# S7CAS-PLEIADES-CARTE-MERE_P20_Flash-Sens.net
KiCad netlist of a schematic drawn in Altium Designer
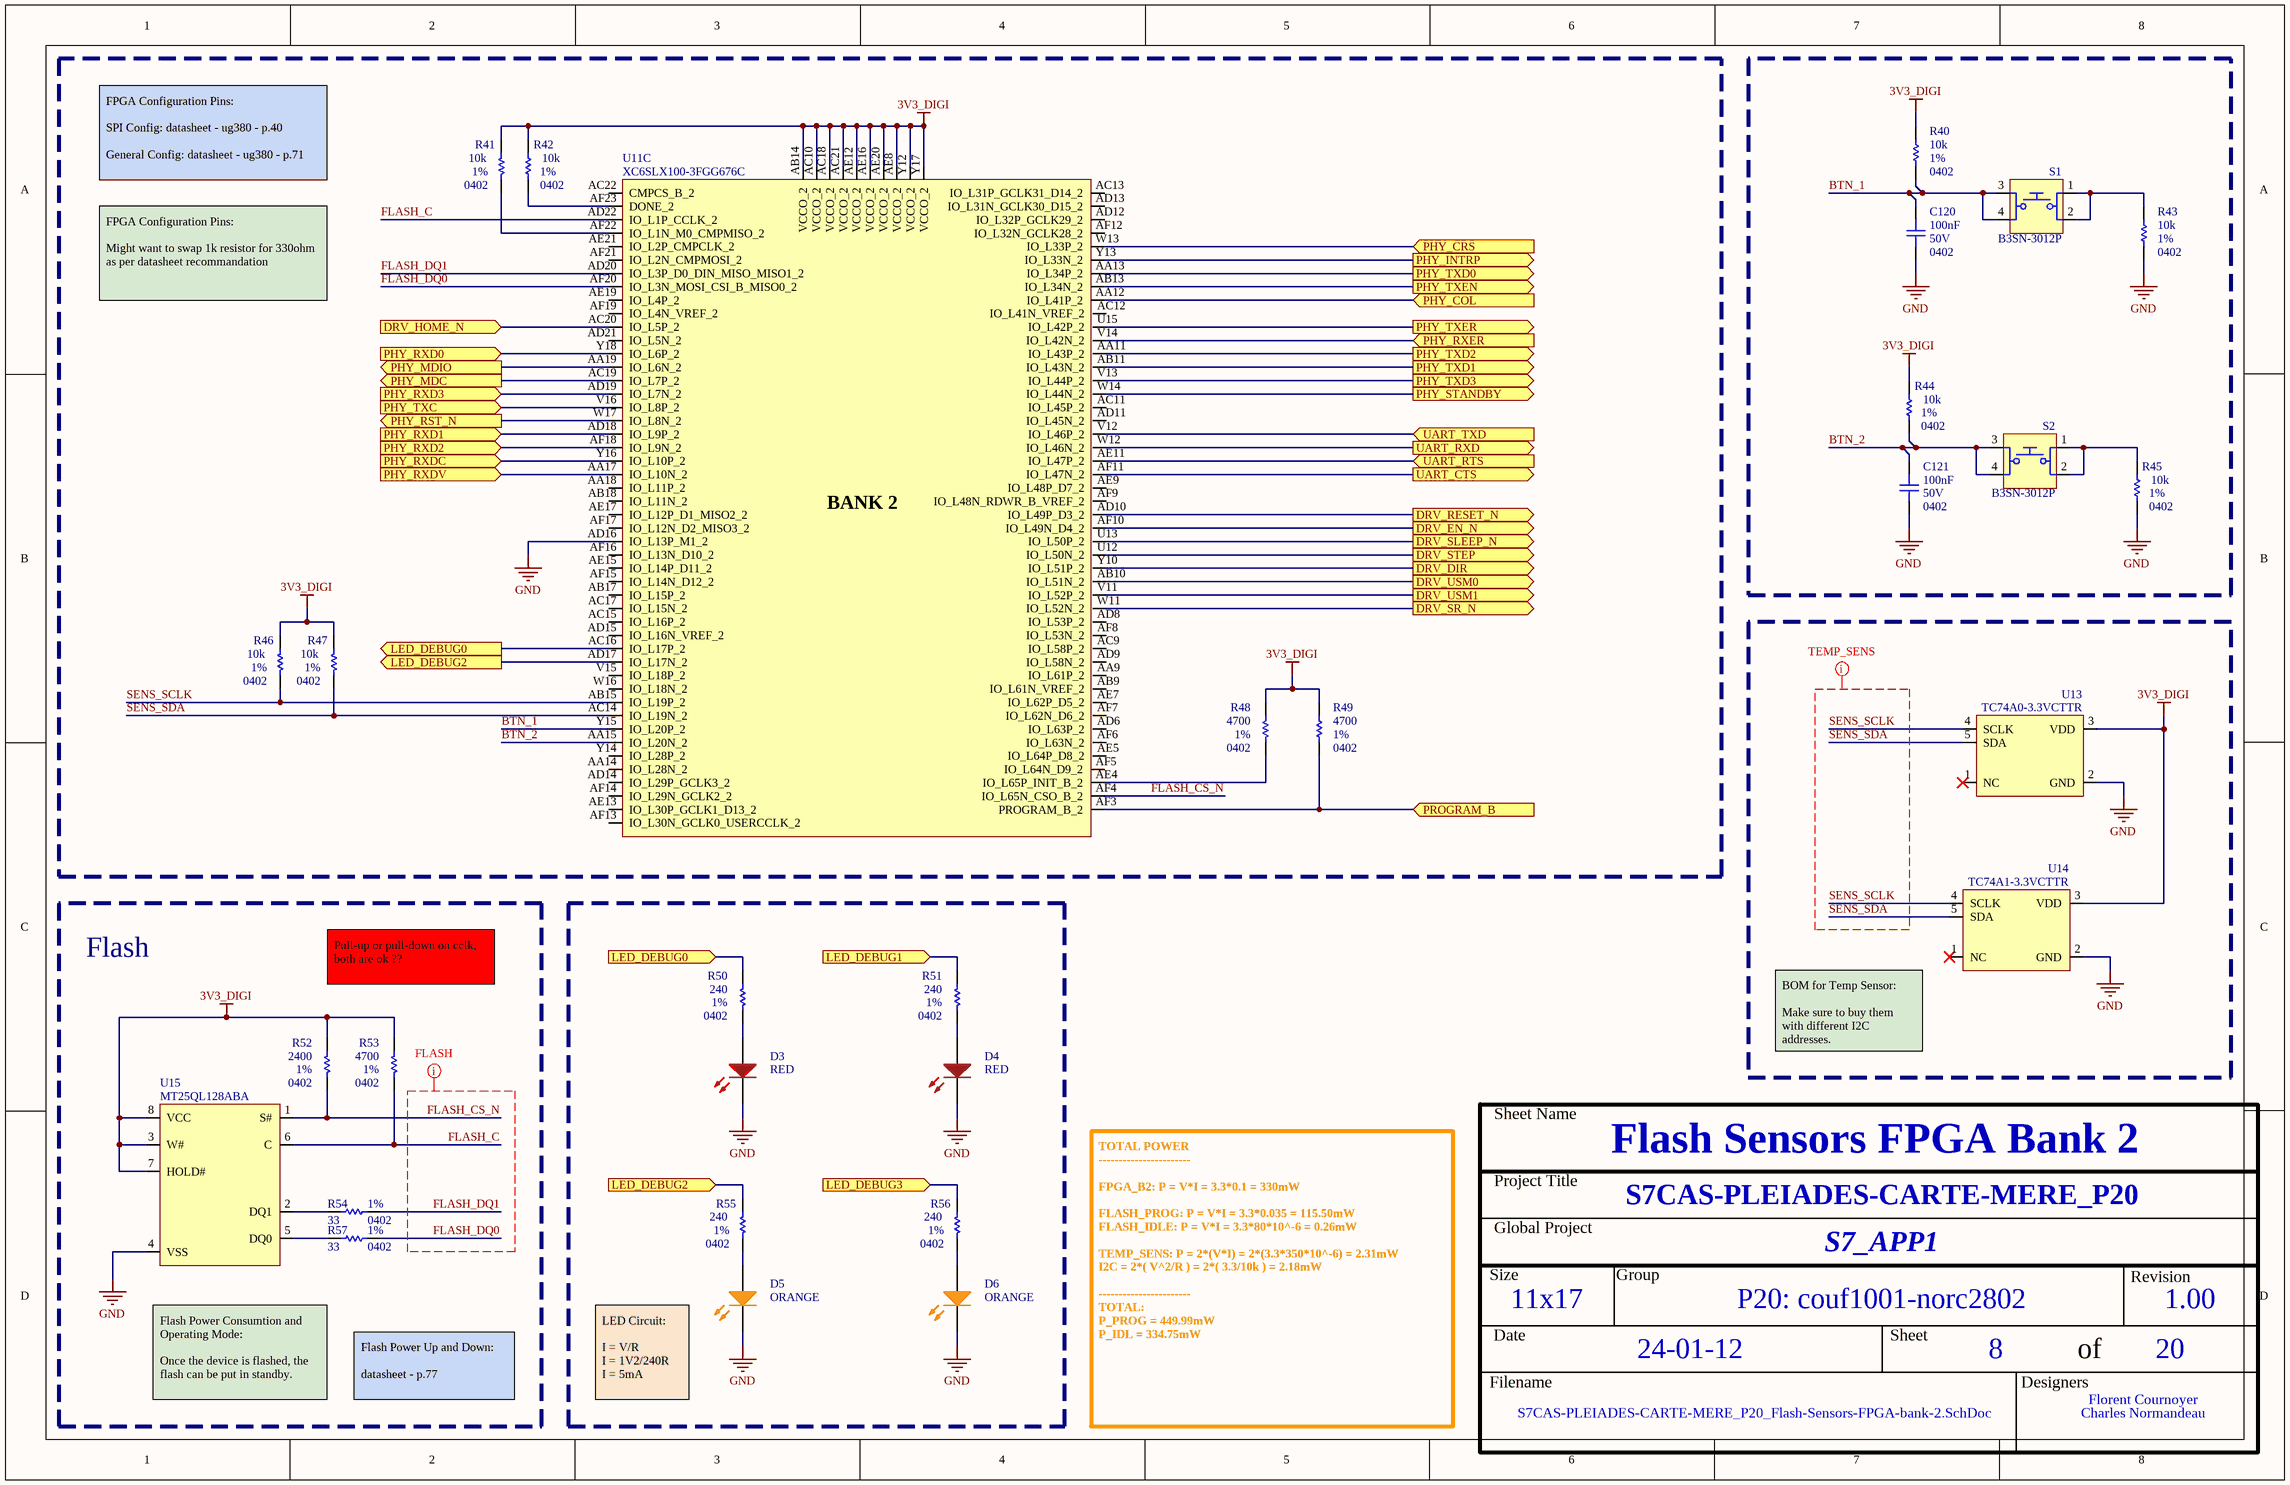
[diagram p0: S7CAS-PLEIADES-CARTE-MERE_P20_Flash-Sensors-FPGA-bank-2.SchDoc]

(export (version "E")
  (design (tool "Eeschema 10.0.6"))
  (components
    (comp (ref "C120")
      (value "100nF")
      (footprint "CAP_0402")
      (description "CAP - 0402")
      (fields
        (field (name "MFG PART NUMBER") "GRM155R61H104KE14")
        (field (name "VOLTAGE") "50V")
        (field (name "PACKAGE") "0402")
        (field (name "CREATEDBY") "Jonathan Bouchard")
      )
      (libsource (lib "S7CAS_LIB2023") (part "CAP - 0402"))
    )
    (comp (ref "C121")
      (value "100nF")
      (footprint "CAP_0402")
      (description "CAP - 0402")
      (fields
        (field (name "MFG PART NUMBER") "GRM155R61H104KE14")
        (field (name "VOLTAGE") "50V")
        (field (name "PACKAGE") "0402")
        (field (name "CREATEDBY") "Jonathan Bouchard")
      )
      (libsource (lib "S7CAS_LIB2023") (part "CAP - 0402"))
    )
    (comp (ref "D3")
      (value "RED")
      (footprint "LED_0603")
      (description "LED - 620nM RED 2mA - 0603")
      (fields
        (field (name "VOLTAGE") "1.8V")
        (field (name "MFG") "ROHM Semiconductor")
        (field (name "CREATEDBY") "Jonathan Bouchard")
      )
      (libsource (lib "S7CAS_LIB2023") (part "LED_SML-311UTT86"))
    )
    (comp (ref "D4")
      (value "RED")
      (footprint "LED_0603")
      (description "LED - 620nM RED 2mA - 0603")
      (fields
        (field (name "VOLTAGE") "1.8V")
        (field (name "MFG") "ROHM Semiconductor")
        (field (name "CREATEDBY") "Jonathan Bouchard")
      )
      (libsource (lib "S7CAS_LIB2023") (part "LED_SML-311UTT86"))
    )
    (comp (ref "D5")
      (value "ORANGE")
      (footprint "LED_0603")
      (description "LED - 611nM ORANGE 2mA - 0603")
      (fields
        (field (name "VOLTAGE") "1.8V")
        (field (name "MFG") "ROHM Semiconductor")
        (field (name "CREATEDBY") "Jonathan Bouchard")
      )
      (libsource (lib "S7CAS_LIB2023") (part "LED_SML-311DTT86"))
    )
    (comp (ref "D6")
      (value "ORANGE")
      (footprint "LED_0603")
      (description "LED - 611nM ORANGE 2mA - 0603")
      (fields
        (field (name "VOLTAGE") "1.8V")
        (field (name "MFG") "ROHM Semiconductor")
        (field (name "CREATEDBY") "Jonathan Bouchard")
      )
      (libsource (lib "S7CAS_LIB2023") (part "LED_SML-311DTT86"))
    )
    (comp (ref "R40")
      (value "10k")
      (footprint "RES_0402")
      (description "RES - 0402")
      (fields
        (field (name "VOLTAGE") "50V")
        (field (name "MFG PART NUMBER") "MCS04020C1002FE000")
        (field (name "PACKAGE") "0402")
        (field (name "PRECISION") "1%")
        (field (name "CREATEDBY") "Jonathan Bouchard")
      )
      (libsource (lib "S7CAS_LIB2023") (part "RES - 0402"))
    )
    (comp (ref "R41")
      (value "10k")
      (footprint "RES_0402")
      (description "RES - 0402")
      (fields
        (field (name "VOLTAGE") "50V")
        (field (name "MFG PART NUMBER") "MCS04020C1002FE000")
        (field (name "PACKAGE") "0402")
        (field (name "PRECISION") "1%")
        (field (name "CREATEDBY") "Jonathan Bouchard")
      )
      (libsource (lib "S7CAS_LIB2023") (part "RES - 0402"))
    )
    (comp (ref "R42")
      (value "10k")
      (footprint "RES_0402")
      (description "RES - 0402")
      (fields
        (field (name "VOLTAGE") "50V")
        (field (name "MFG PART NUMBER") "MCS04020C1002FE000")
        (field (name "PACKAGE") "0402")
        (field (name "PRECISION") "1%")
        (field (name "CREATEDBY") "Jonathan Bouchard")
      )
      (libsource (lib "S7CAS_LIB2023") (part "RES - 0402"))
    )
    (comp (ref "R43")
      (value "10k")
      (footprint "RES_0402")
      (description "RES - 0402")
      (fields
        (field (name "VOLTAGE") "50V")
        (field (name "MFG PART NUMBER") "MCS04020C1002FE000")
        (field (name "PACKAGE") "0402")
        (field (name "PRECISION") "1%")
        (field (name "CREATEDBY") "Jonathan Bouchard")
      )
      (libsource (lib "S7CAS_LIB2023") (part "RES - 0402"))
    )
    (comp (ref "R44")
      (value "10k")
      (footprint "RES_0402")
      (description "RES - 0402")
      (fields
        (field (name "VOLTAGE") "50V")
        (field (name "MFG PART NUMBER") "MCS04020C1002FE000")
        (field (name "PACKAGE") "0402")
        (field (name "PRECISION") "1%")
        (field (name "CREATEDBY") "Jonathan Bouchard")
      )
      (libsource (lib "S7CAS_LIB2023") (part "RES - 0402"))
    )
    (comp (ref "R45")
      (value "10k")
      (footprint "RES_0402")
      (description "RES - 0402")
      (fields
        (field (name "VOLTAGE") "50V")
        (field (name "MFG PART NUMBER") "MCS04020C1002FE000")
        (field (name "PACKAGE") "0402")
        (field (name "PRECISION") "1%")
        (field (name "CREATEDBY") "Jonathan Bouchard")
      )
      (libsource (lib "S7CAS_LIB2023") (part "RES - 0402"))
    )
    (comp (ref "R46")
      (value "10k")
      (footprint "RES_0402")
      (description "RES - 0402")
      (fields
        (field (name "VOLTAGE") "50V")
        (field (name "MFG PART NUMBER") "MCS04020C1002FE000")
        (field (name "PACKAGE") "0402")
        (field (name "PRECISION") "1%")
        (field (name "CREATEDBY") "Jonathan Bouchard")
      )
      (libsource (lib "S7CAS_LIB2023") (part "RES - 0402"))
    )
    (comp (ref "R47")
      (value "10k")
      (footprint "RES_0402")
      (description "RES - 0402")
      (fields
        (field (name "VOLTAGE") "50V")
        (field (name "MFG PART NUMBER") "MCS04020C1002FE000")
        (field (name "PACKAGE") "0402")
        (field (name "PRECISION") "1%")
        (field (name "CREATEDBY") "Jonathan Bouchard")
      )
      (libsource (lib "S7CAS_LIB2023") (part "RES - 0402"))
    )
    (comp (ref "R48")
      (value "4700")
      (footprint "RES_0402")
      (description "RES - 0402")
      (fields
        (field (name "VOLTAGE") "50V")
        (field (name "MFG PART NUMBER") "TBD")
        (field (name "PACKAGE") "0402")
        (field (name "PRECISION") "1%")
        (field (name "CREATEDBY") "Jonathan Bouchard")
      )
      (libsource (lib "S7CAS_LIB2023") (part "RES - 0402"))
    )
    (comp (ref "R49")
      (value "4700")
      (footprint "RES_0402")
      (description "RES - 0402")
      (fields
        (field (name "VOLTAGE") "50V")
        (field (name "MFG PART NUMBER") "TBD")
        (field (name "PACKAGE") "0402")
        (field (name "PRECISION") "1%")
        (field (name "CREATEDBY") "Jonathan Bouchard")
      )
      (libsource (lib "S7CAS_LIB2023") (part "RES - 0402"))
    )
    (comp (ref "R50")
      (value "240")
      (footprint "RES_0402")
      (description "RES - 0402")
      (fields
        (field (name "VOLTAGE") "50V")
        (field (name "MFG PART NUMBER") "ERA-2AEB241X")
        (field (name "PACKAGE") "0402")
        (field (name "PRECISION") "1%")
        (field (name "CREATEDBY") "Jonathan Bouchard")
      )
      (libsource (lib "S7CAS_LIB2023") (part "RES - 0402"))
    )
    (comp (ref "R51")
      (value "240")
      (footprint "RES_0402")
      (description "RES - 0402")
      (fields
        (field (name "VOLTAGE") "50V")
        (field (name "MFG PART NUMBER") "ERA-2AEB241X")
        (field (name "PACKAGE") "0402")
        (field (name "PRECISION") "1%")
        (field (name "CREATEDBY") "Jonathan Bouchard")
      )
      (libsource (lib "S7CAS_LIB2023") (part "RES - 0402"))
    )
    (comp (ref "R52")
      (value "2400")
      (footprint "RES_0402")
      (description "RES - 0402")
      (fields
        (field (name "VOLTAGE") "50V")
        (field (name "POWER") "1/16W")
        (field (name "PACKAGE") "0402")
        (field (name "PRECISION") "1%")
        (field (name "CREATEDBY") "Jonathan Bouchard")
      )
      (libsource (lib "S7CAS_LIB2023") (part "RES - 0402"))
    )
    (comp (ref "R53")
      (value "4700")
      (footprint "RES_0402")
      (description "RES - 0402")
      (fields
        (field (name "VOLTAGE") "50V")
        (field (name "MFG PART NUMBER") "TBD")
        (field (name "PACKAGE") "0402")
        (field (name "PRECISION") "1%")
        (field (name "CREATEDBY") "Jonathan Bouchard")
      )
      (libsource (lib "S7CAS_LIB2023") (part "RES - 0402"))
    )
    (comp (ref "R54")
      (value "33")
      (footprint "RES_0402")
      (description "RES - 0402")
      (fields
        (field (name "VOLTAGE") "50V")
        (field (name "MFG PART NUMBER") "CRCW040233R0FKEDC")
        (field (name "PACKAGE") "0402")
        (field (name "PRECISION") "1%")
        (field (name "CREATEDBY") "Jonathan Bouchard")
      )
      (libsource (lib "S7CAS_LIB2023") (part "RES - 0402"))
    )
    (comp (ref "R55")
      (value "240")
      (footprint "RES_0402")
      (description "RES - 0402")
      (fields
        (field (name "VOLTAGE") "50V")
        (field (name "MFG PART NUMBER") "ERA-2AEB241X")
        (field (name "PACKAGE") "0402")
        (field (name "PRECISION") "1%")
        (field (name "CREATEDBY") "Jonathan Bouchard")
      )
      (libsource (lib "S7CAS_LIB2023") (part "RES - 0402"))
    )
    (comp (ref "R56")
      (value "240")
      (footprint "RES_0402")
      (description "RES - 0402")
      (fields
        (field (name "VOLTAGE") "50V")
        (field (name "MFG PART NUMBER") "ERA-2AEB241X")
        (field (name "PACKAGE") "0402")
        (field (name "PRECISION") "1%")
        (field (name "CREATEDBY") "Jonathan Bouchard")
      )
      (libsource (lib "S7CAS_LIB2023") (part "RES - 0402"))
    )
    (comp (ref "R57")
      (value "33")
      (footprint "RES_0402")
      (description "RES - 0402")
      (fields
        (field (name "VOLTAGE") "50V")
        (field (name "MFG PART NUMBER") "CRCW040233R0FKEDC")
        (field (name "PACKAGE") "0402")
        (field (name "PRECISION") "1%")
        (field (name "CREATEDBY") "Jonathan Bouchard")
      )
      (libsource (lib "S7CAS_LIB2023") (part "RES - 0402"))
    )
    (comp (ref "S1")
      (value "B3SN-3012P")
      (footprint "SWI_TACT_B3SN-3012P")
      (description "SWI - SWITCH TACTILE SPST-NO 0.05A 24V -SMD")
      (fields
        (field (name "CREATEDBY/DATE") "Olivier Bernard / 5/12/2017")
        (field (name "VERIFIEDBY") "Caroline Paulin / 11 juillet 2018")
      )
      (libsource (lib "S7CAS_LIB2023") (part "SWI_TACT_B3SN-3012P_1"))
    )
    (comp (ref "S2")
      (value "B3SN-3012P")
      (footprint "SWI_TACT_B3SN-3012P")
      (description "SWI - SWITCH TACTILE SPST-NO 0.05A 24V -SMD")
      (fields
        (field (name "CREATEDBY/DATE") "Olivier Bernard / 5/12/2017")
        (field (name "VERIFIEDBY") "Caroline Paulin / 11 juillet 2018")
      )
      (libsource (lib "S7CAS_LIB2023") (part "SWI_TACT_B3SN-3012P_1"))
    )
    (comp (ref "U11")
      (value "XC6SLX100-3FGG676C")
      (footprint "FPGA_XILINX_FGG676")
      (description "FPGA - XILINX SPARTAN 6 480 I/O - BGA-676")
      (fields
        (field (name "VOLTAGE") "1.14 V ~ 1.26 V")
        (field (name "MFG") "Xilinx")
        (field (name "CREATEDBY") "Jonathan Bouchard")
      )
      (libsource (lib "S7CAS_LIB2023") (part "FPGA_XC6SLX100-3FGG676C"))
    )
    (comp (ref "U13")
      (value "TC74A0-3.3VCTTR")
      (footprint "SEN_TEMP_TC74A0-3.3VCTTR")
      (description "SENS - TEMPERATURE SENSOR I2C/SMBUS - SOT23-5")
      (fields
        (field (name "VOLTAGE") "2.7 V ~ 5.5 V")
        (field (name "MFG") "Microchip")
        (field (name "CREATEDBY") "Jonathan Bouchard")
      )
      (libsource (lib "S7CAS_LIB2023") (part "SENS_TEMP_TC74A0-3.3VCTTR"))
    )
    (comp (ref "U14")
      (value "TC74A1-3.3VCTTR")
      (footprint "SEN_TEMP_TC74A0-3.3VCTTR")
      (description "SENS - TEMPERATURE SENSOR I2C/SMBUS - SOT23-5")
      (fields
        (field (name "VOLTAGE") "2.7 V ~ 5.5 V")
        (field (name "MFG") "Microchip")
        (field (name "CREATEDBY") "Jonathan Bouchard")
      )
      (libsource (lib "S7CAS_LIB2023") (part "SENS_TEMP_TC74A0-3.3VCTTR"))
    )
    (comp (ref "U15")
      (value "MT25QL128ABA")
      (footprint "FLASH_MT25QL128ABA")
      (description "MT25QL128ABA - 128Mb, 3V Multiple I/O Serial Flash Memory - Package code : SE")
      (libsource (lib "LIB_TEMP_P20_CHARLES_NORMANDEAU_SCH") (part "FLASH_MT25QL128ABA"))
    )
  )
  (nets
    (net (code "2") (name "/BTN_1") (class "Default")
      (node (ref "C120") (pin "2") (pinfunction "2_2") (pintype "passive"))
      (node (ref "R40") (pin "1") (pinfunction "1_1") (pintype "passive"))
      (node (ref "S1") (pin "3") (pinfunction "3_3") (pintype "passive"))
      (node (ref "S1") (pin "4") (pinfunction "4_4") (pintype "passive"))
      (node (ref "U11") (pin "Y15") (pinfunction "IO_L20P_2_Y15") (pintype "passive"))
    )
    (net (code "3") (name "/BTN_2") (class "Default")
      (node (ref "C121") (pin "2") (pinfunction "2_2") (pintype "passive"))
      (node (ref "R44") (pin "1") (pinfunction "1_1") (pintype "passive"))
      (node (ref "S2") (pin "3") (pinfunction "3_3") (pintype "passive"))
      (node (ref "S2") (pin "4") (pinfunction "4_4") (pintype "passive"))
      (node (ref "U11") (pin "AA15") (pinfunction "IO_L20N_2_AA15") (pintype "passive"))
    )
    (net (code "4") (name "/DRV_DIR") (class "Default")
      (node (ref "U11") (pin "Y10") (pinfunction "IO_L51P_2_Y10") (pintype "passive"))
    )
    (net (code "5") (name "/DRV_EN_N") (class "Default")
      (node (ref "U11") (pin "AF10") (pinfunction "IO_L49N_D4_2_AF10") (pintype "passive"))
    )
    (net (code "6") (name "/DRV_HOME_N") (class "Default")
      (node (ref "U11") (pin "AC20") (pinfunction "IO_L5P_2_AC20") (pintype "passive"))
    )
    (net (code "7") (name "/DRV_RESET_N") (class "Default")
      (node (ref "U11") (pin "AD10") (pinfunction "IO_L49P_D3_2_AD10") (pintype "passive"))
    )
    (net (code "8") (name "/DRV_SLEEP_N") (class "Default")
      (node (ref "U11") (pin "U13") (pinfunction "IO_L50P_2_U13") (pintype "passive"))
    )
    (net (code "9") (name "/DRV_SR_N") (class "Default")
      (node (ref "U11") (pin "W11") (pinfunction "IO_L52N_2_W11") (pintype "passive"))
    )
    (net (code "10") (name "/DRV_STEP") (class "Default")
      (node (ref "U11") (pin "U12") (pinfunction "IO_L50N_2_U12") (pintype "passive"))
    )
    (net (code "11") (name "/DRV_USM0") (class "Default")
      (node (ref "U11") (pin "AB10") (pinfunction "IO_L51N_2_AB10") (pintype "passive"))
    )
    (net (code "12") (name "/DRV_USM1") (class "Default")
      (node (ref "U11") (pin "V11") (pinfunction "IO_L52P_2_V11") (pintype "passive"))
    )
    (net (code "13") (name "/FLASH_C") (class "Default")
      (node (ref "R53") (pin "1") (pinfunction "1_1") (pintype "passive"))
      (node (ref "U11") (pin "AD22") (pinfunction "IO_L1P_CCLK_2_AD22") (pintype "passive"))
      (node (ref "U15") (pin "6") (pinfunction "C_6") (pintype "passive"))
    )
    (net (code "14") (name "/FLASH_CS_N") (class "Default")
      (node (ref "R52") (pin "1") (pinfunction "1_1") (pintype "passive"))
      (node (ref "U11") (pin "AF4") (pinfunction "IO_L65N_CSO_B_2_AF4") (pintype "passive"))
      (node (ref "U15") (pin "1") (pinfunction "S#_1") (pintype "passive"))
    )
    (net (code "15") (name "/FLASH_DQ0") (class "Default")
      (node (ref "R57") (pin "1") (pinfunction "1_1") (pintype "passive"))
      (node (ref "U11") (pin "AF20") (pinfunction "IO_L3N_MOSI_CSI_B_MISO0_2_AF20") (pintype "passive"))
    )
    (net (code "16") (name "/FLASH_DQ1") (class "Default")
      (node (ref "R54") (pin "1") (pinfunction "1_1") (pintype "passive"))
      (node (ref "U11") (pin "AD20") (pinfunction "IO_L3P_D0_DIN_MISO_MISO1_2_AD20") (pintype "passive"))
    )
    (net (code "17") (name "/LED_DEBUG0") (class "Default")
      (node (ref "R50") (pin "2") (pinfunction "2_2") (pintype "passive"))
      (node (ref "U11") (pin "AC16") (pinfunction "IO_L17P_2_AC16") (pintype "passive"))
    )
    (net (code "18") (name "/LED_DEBUG1") (class "Default")
      (node (ref "R51") (pin "2") (pinfunction "2_2") (pintype "passive"))
    )
    (net (code "19") (name "/LED_DEBUG2") (class "Default")
      (node (ref "R55") (pin "2") (pinfunction "2_2") (pintype "passive"))
      (node (ref "U11") (pin "AD17") (pinfunction "IO_L17N_2_AD17") (pintype "passive"))
    )
    (net (code "20") (name "/LED_DEBUG3") (class "Default")
      (node (ref "R56") (pin "2") (pinfunction "2_2") (pintype "passive"))
    )
    (net (code "21") (name "/PHY_COL") (class "Default")
      (node (ref "U11") (pin "AA12") (pinfunction "IO_L41P_2_AA12") (pintype "passive"))
    )
    (net (code "22") (name "/PHY_CRS") (class "Default")
      (node (ref "U11") (pin "W13") (pinfunction "IO_L33P_2_W13") (pintype "passive"))
    )
    (net (code "23") (name "/PHY_INTRP") (class "Default")
      (node (ref "U11") (pin "Y13") (pinfunction "IO_L33N_2_Y13") (pintype "passive"))
    )
    (net (code "24") (name "/PHY_MDC") (class "Default")
      (node (ref "U11") (pin "AC19") (pinfunction "IO_L7P_2_AC19") (pintype "passive"))
    )
    (net (code "25") (name "/PHY_MDIO") (class "Default")
      (node (ref "U11") (pin "AA19") (pinfunction "IO_L6N_2_AA19") (pintype "passive"))
    )
    (net (code "26") (name "/PHY_RST_N") (class "Default")
      (node (ref "U11") (pin "W17") (pinfunction "IO_L8N_2_W17") (pintype "passive"))
    )
    (net (code "27") (name "/PHY_RXD0") (class "Default")
      (node (ref "U11") (pin "Y18") (pinfunction "IO_L6P_2_Y18") (pintype "passive"))
    )
    (net (code "28") (name "/PHY_RXD1") (class "Default")
      (node (ref "U11") (pin "AD18") (pinfunction "IO_L9P_2_AD18") (pintype "passive"))
    )
    (net (code "29") (name "/PHY_RXD2") (class "Default")
      (node (ref "U11") (pin "AF18") (pinfunction "IO_L9N_2_AF18") (pintype "passive"))
    )
    (net (code "30") (name "/PHY_RXD3") (class "Default")
      (node (ref "U11") (pin "AD19") (pinfunction "IO_L7N_2_AD19") (pintype "passive"))
    )
    (net (code "31") (name "/PHY_RXDC") (class "Default")
      (node (ref "U11") (pin "Y16") (pinfunction "IO_L10P_2_Y16") (pintype "passive"))
    )
    (net (code "32") (name "/PHY_RXDV") (class "Default")
      (node (ref "U11") (pin "AA17") (pinfunction "IO_L10N_2_AA17") (pintype "passive"))
    )
    (net (code "33") (name "/PHY_RXER") (class "Default")
      (node (ref "U11") (pin "V14") (pinfunction "IO_L42N_2_V14") (pintype "passive"))
    )
    (net (code "34") (name "/PHY_STANDBY") (class "Default")
      (node (ref "U11") (pin "W14") (pinfunction "IO_L44N_2_W14") (pintype "passive"))
    )
    (net (code "35") (name "/PHY_TXC") (class "Default")
      (node (ref "U11") (pin "V16") (pinfunction "IO_L8P_2_V16") (pintype "passive"))
    )
    (net (code "36") (name "/PHY_TXD0") (class "Default")
      (node (ref "U11") (pin "AA13") (pinfunction "IO_L34P_2_AA13") (pintype "passive"))
    )
    (net (code "37") (name "/PHY_TXD1") (class "Default")
      (node (ref "U11") (pin "AB11") (pinfunction "IO_L43N_2_AB11") (pintype "passive"))
    )
    (net (code "38") (name "/PHY_TXD2") (class "Default")
      (node (ref "U11") (pin "AA11") (pinfunction "IO_L43P_2_AA11") (pintype "passive"))
    )
    (net (code "39") (name "/PHY_TXD3") (class "Default")
      (node (ref "U11") (pin "V13") (pinfunction "IO_L44P_2_V13") (pintype "passive"))
    )
    (net (code "40") (name "/PHY_TXEN") (class "Default")
      (node (ref "U11") (pin "AB13") (pinfunction "IO_L34N_2_AB13") (pintype "passive"))
    )
    (net (code "41") (name "/PHY_TXER") (class "Default")
      (node (ref "U11") (pin "U15") (pinfunction "IO_L42P_2_U15") (pintype "passive"))
    )
    (net (code "42") (name "/PROGRAM_B") (class "Default")
      (node (ref "R49") (pin "1") (pinfunction "1_1") (pintype "passive"))
      (node (ref "U11") (pin "AF3") (pinfunction "PROGRAM_B_2_AF3") (pintype "passive"))
    )
    (net (code "43") (name "/SENS_SCLK") (class "Default")
      (node (ref "R46") (pin "1") (pinfunction "1_1") (pintype "passive"))
      (node (ref "U11") (pin "AB15") (pinfunction "IO_L19P_2_AB15") (pintype "passive"))
      (node (ref "U13") (pin "4") (pinfunction "SCLK_4") (pintype "passive"))
      (node (ref "U14") (pin "4") (pinfunction "SCLK_4") (pintype "passive"))
    )
    (net (code "44") (name "/SENS_SDA") (class "Default")
      (node (ref "R47") (pin "1") (pinfunction "1_1") (pintype "passive"))
      (node (ref "U11") (pin "AC14") (pinfunction "IO_L19N_2_AC14") (pintype "passive"))
      (node (ref "U13") (pin "5") (pinfunction "SDA_5") (pintype "passive"))
      (node (ref "U14") (pin "5") (pinfunction "SDA_5") (pintype "passive"))
    )
    (net (code "45") (name "/UART_CTS") (class "Default")
      (node (ref "U11") (pin "AF11") (pinfunction "IO_L47N_2_AF11") (pintype "passive"))
    )
    (net (code "46") (name "/UART_RTS") (class "Default")
      (node (ref "U11") (pin "AE11") (pinfunction "IO_L47P_2_AE11") (pintype "passive"))
    )
    (net (code "47") (name "/UART_RXD") (class "Default")
      (node (ref "U11") (pin "W12") (pinfunction "IO_L46N_2_W12") (pintype "passive"))
    )
    (net (code "48") (name "/UART_TXD") (class "Default")
      (node (ref "U11") (pin "V12") (pinfunction "IO_L46P_2_V12") (pintype "passive"))
    )
    (net (code "49") (name "3V3_DIGI") (class "Default")
      (node (ref "R40") (pin "2") (pinfunction "2_2") (pintype "passive"))
      (node (ref "R41") (pin "2") (pinfunction "2_2") (pintype "passive"))
      (node (ref "R42") (pin "2") (pinfunction "2_2") (pintype "passive"))
      (node (ref "R44") (pin "2") (pinfunction "2_2") (pintype "passive"))
      (node (ref "R46") (pin "2") (pinfunction "2_2") (pintype "passive"))
      (node (ref "R47") (pin "2") (pinfunction "2_2") (pintype "passive"))
      (node (ref "R48") (pin "2") (pinfunction "2_2") (pintype "passive"))
      (node (ref "R49") (pin "2") (pinfunction "2_2") (pintype "passive"))
      (node (ref "R52") (pin "2") (pinfunction "2_2") (pintype "passive"))
      (node (ref "R53") (pin "2") (pinfunction "2_2") (pintype "passive"))
      (node (ref "U11") (pin "AB14") (pinfunction "VCCO_2_AB14") (pintype "passive"))
      (node (ref "U11") (pin "AC10") (pinfunction "VCCO_2_AC10") (pintype "passive"))
      (node (ref "U11") (pin "AC18") (pinfunction "VCCO_2_AC18") (pintype "passive"))
      (node (ref "U11") (pin "AC21") (pinfunction "VCCO_2_AC21") (pintype "passive"))
      (node (ref "U11") (pin "AE12") (pinfunction "VCCO_2_AE12") (pintype "passive"))
      (node (ref "U11") (pin "AE16") (pinfunction "VCCO_2_AE16") (pintype "passive"))
      (node (ref "U11") (pin "AE20") (pinfunction "VCCO_2_AE20") (pintype "passive"))
      (node (ref "U11") (pin "AE8") (pinfunction "VCCO_2_AE8") (pintype "passive"))
      (node (ref "U11") (pin "Y12") (pinfunction "VCCO_2_Y12") (pintype "passive"))
      (node (ref "U11") (pin "Y17") (pinfunction "VCCO_2_Y17") (pintype "passive"))
      (node (ref "U13") (pin "3") (pinfunction "VDD_3") (pintype "passive"))
      (node (ref "U14") (pin "3") (pinfunction "VDD_3") (pintype "passive"))
      (node (ref "U15") (pin "3") (pinfunction "W#_3") (pintype "passive"))
      (node (ref "U15") (pin "7") (pinfunction "HOLD#_7") (pintype "passive"))
      (node (ref "U15") (pin "8") (pinfunction "VCC_8") (pintype "passive"))
    )
    (net (code "50") (name "GND") (class "Default")
      (node (ref "C120") (pin "1") (pinfunction "1_1") (pintype "passive"))
      (node (ref "C121") (pin "1") (pinfunction "1_1") (pintype "passive"))
      (node (ref "D3") (pin "K") (pinfunction "K_K") (pintype "passive"))
      (node (ref "D4") (pin "K") (pinfunction "K_K") (pintype "passive"))
      (node (ref "D5") (pin "K") (pinfunction "K_K") (pintype "passive"))
      (node (ref "D6") (pin "K") (pinfunction "K_K") (pintype "passive"))
      (node (ref "R43") (pin "1") (pinfunction "1_1") (pintype "passive"))
      (node (ref "R45") (pin "1") (pinfunction "1_1") (pintype "passive"))
      (node (ref "U11") (pin "AD16") (pinfunction "IO_L13P_M1_2_AD16") (pintype "passive"))
      (node (ref "U13") (pin "2") (pinfunction "GND_2") (pintype "passive"))
      (node (ref "U14") (pin "2") (pinfunction "GND_2") (pintype "passive"))
      (node (ref "U15") (pin "4") (pinfunction "VSS_4") (pintype "passive"))
    )
    (net (code "51") (name "Net-(D3-PadA)") (class "Default")
      (node (ref "D3") (pin "A") (pinfunction "A_A") (pintype "passive"))
      (node (ref "R50") (pin "1") (pinfunction "1_1") (pintype "passive"))
    )
    (net (code "52") (name "Net-(D4-PadA)") (class "Default")
      (node (ref "D4") (pin "A") (pinfunction "A_A") (pintype "passive"))
      (node (ref "R51") (pin "1") (pinfunction "1_1") (pintype "passive"))
    )
    (net (code "53") (name "Net-(D5-PadA)") (class "Default")
      (node (ref "D5") (pin "A") (pinfunction "A_A") (pintype "passive"))
      (node (ref "R55") (pin "1") (pinfunction "1_1") (pintype "passive"))
    )
    (net (code "54") (name "Net-(D6-PadA)") (class "Default")
      (node (ref "D6") (pin "A") (pinfunction "A_A") (pintype "passive"))
      (node (ref "R56") (pin "1") (pinfunction "1_1") (pintype "passive"))
    )
    (net (code "55") (name "Net-(R43-Pad2)") (class "Default")
      (node (ref "R43") (pin "2") (pinfunction "2_2") (pintype "passive"))
      (node (ref "S1") (pin "1") (pinfunction "1_1") (pintype "passive"))
      (node (ref "S1") (pin "2") (pinfunction "2_2") (pintype "passive"))
    )
    (net (code "56") (name "Net-(R45-Pad2)") (class "Default")
      (node (ref "R45") (pin "2") (pinfunction "2_2") (pintype "passive"))
      (node (ref "S2") (pin "1") (pinfunction "1_1") (pintype "passive"))
      (node (ref "S2") (pin "2") (pinfunction "2_2") (pintype "passive"))
    )
    (net (code "57") (name "Net-(U11C-DONE_2)") (class "Default")
      (node (ref "R42") (pin "1") (pinfunction "1_1") (pintype "passive"))
      (node (ref "U11") (pin "AF23") (pinfunction "DONE_2_AF23") (pintype "passive"))
    )
    (net (code "58") (name "Net-(U11C-IO_L1N_M0_CMPMISO_2)") (class "Default")
      (node (ref "R41") (pin "1") (pinfunction "1_1") (pintype "passive"))
      (node (ref "U11") (pin "AF22") (pinfunction "IO_L1N_M0_CMPMISO_2_AF22") (pintype "passive"))
    )
    (net (code "59") (name "Net-(U11C-IO_L65P_INIT_B_2)") (class "Default")
      (node (ref "R48") (pin "1") (pinfunction "1_1") (pintype "passive"))
      (node (ref "U11") (pin "AE4") (pinfunction "IO_L65P_INIT_B_2_AE4") (pintype "passive"))
    )
    (net (code "60") (name "Net-(U15-DQ0)") (class "Default")
      (node (ref "R57") (pin "2") (pinfunction "2_2") (pintype "passive"))
      (node (ref "U15") (pin "5") (pinfunction "DQ0_5") (pintype "passive"))
    )
    (net (code "61") (name "Net-(U15-DQ1)") (class "Default")
      (node (ref "R54") (pin "2") (pinfunction "2_2") (pintype "passive"))
      (node (ref "U15") (pin "2") (pinfunction "DQ1_2") (pintype "passive"))
    )
    (net (code "62") (name "unconnected-(U11C-CMPCS_B_2-PadAC22)") (class "Default")
      (node (ref "U11") (pin "AC22") (pinfunction "CMPCS_B_2_AC22") (pintype "passive"))
    )
    (net (code "63") (name "unconnected-(U11C-IO_L2N_CMPMOSI_2-PadAF21)") (class "Default")
      (node (ref "U11") (pin "AF21") (pinfunction "IO_L2N_CMPMOSI_2_AF21") (pintype "passive"))
    )
    (net (code "64") (name "unconnected-(U11C-IO_L2P_CMPCLK_2-PadAE21)") (class "Default")
      (node (ref "U11") (pin "AE21") (pinfunction "IO_L2P_CMPCLK_2_AE21") (pintype "passive"))
    )
    (net (code "65") (name "unconnected-(U11C-IO_L4N_VREF_2-PadAF19)") (class "Default")
      (node (ref "U11") (pin "AF19") (pinfunction "IO_L4N_VREF_2_AF19") (pintype "passive"))
    )
    (net (code "66") (name "unconnected-(U11C-IO_L4P_2-PadAE19)") (class "Default")
      (node (ref "U11") (pin "AE19") (pinfunction "IO_L4P_2_AE19") (pintype "passive"))
    )
    (net (code "67") (name "unconnected-(U11C-IO_L5N_2-PadAD21)") (class "Default")
      (node (ref "U11") (pin "AD21") (pinfunction "IO_L5N_2_AD21") (pintype "passive"))
    )
    (net (code "68") (name "unconnected-(U11C-IO_L11N_2-PadAB18)") (class "Default")
      (node (ref "U11") (pin "AB18") (pinfunction "IO_L11N_2_AB18") (pintype "passive"))
    )
    (net (code "69") (name "unconnected-(U11C-IO_L11P_2-PadAA18)") (class "Default")
      (node (ref "U11") (pin "AA18") (pinfunction "IO_L11P_2_AA18") (pintype "passive"))
    )
    (net (code "70") (name "unconnected-(U11C-IO_L12N_D2_MISO3_2-PadAF17)") (class "Default")
      (node (ref "U11") (pin "AF17") (pinfunction "IO_L12N_D2_MISO3_2_AF17") (pintype "passive"))
    )
    (net (code "71") (name "unconnected-(U11C-IO_L12P_D1_MISO2_2-PadAE17)") (class "Default")
      (node (ref "U11") (pin "AE17") (pinfunction "IO_L12P_D1_MISO2_2_AE17") (pintype "passive"))
    )
    (net (code "72") (name "unconnected-(U11C-IO_L13N_D10_2-PadAF16)") (class "Default")
      (node (ref "U11") (pin "AF16") (pinfunction "IO_L13N_D10_2_AF16") (pintype "passive"))
    )
    (net (code "73") (name "unconnected-(U11C-IO_L14N_D12_2-PadAF15)") (class "Default")
      (node (ref "U11") (pin "AF15") (pinfunction "IO_L14N_D12_2_AF15") (pintype "passive"))
    )
    (net (code "74") (name "unconnected-(U11C-IO_L14P_D11_2-PadAE15)") (class "Default")
      (node (ref "U11") (pin "AE15") (pinfunction "IO_L14P_D11_2_AE15") (pintype "passive"))
    )
    (net (code "75") (name "unconnected-(U11C-IO_L15N_2-PadAC17)") (class "Default")
      (node (ref "U11") (pin "AC17") (pinfunction "IO_L15N_2_AC17") (pintype "passive"))
    )
    (net (code "76") (name "unconnected-(U11C-IO_L15P_2-PadAB17)") (class "Default")
      (node (ref "U11") (pin "AB17") (pinfunction "IO_L15P_2_AB17") (pintype "passive"))
    )
    (net (code "77") (name "unconnected-(U11C-IO_L16N_VREF_2-PadAD15)") (class "Default")
      (node (ref "U11") (pin "AD15") (pinfunction "IO_L16N_VREF_2_AD15") (pintype "passive"))
    )
    (net (code "78") (name "unconnected-(U11C-IO_L16P_2-PadAC15)") (class "Default")
      (node (ref "U11") (pin "AC15") (pinfunction "IO_L16P_2_AC15") (pintype "passive"))
    )
    (net (code "79") (name "unconnected-(U11C-IO_L18N_2-PadW16)") (class "Default")
      (node (ref "U11") (pin "W16") (pinfunction "IO_L18N_2_W16") (pintype "passive"))
    )
    (net (code "80") (name "unconnected-(U11C-IO_L18P_2-PadV15)") (class "Default")
      (node (ref "U11") (pin "V15") (pinfunction "IO_L18P_2_V15") (pintype "passive"))
    )
    (net (code "81") (name "unconnected-(U11C-IO_L28N_2-PadAA14)") (class "Default")
      (node (ref "U11") (pin "AA14") (pinfunction "IO_L28N_2_AA14") (pintype "passive"))
    )
    (net (code "82") (name "unconnected-(U11C-IO_L28P_2-PadY14)") (class "Default")
      (node (ref "U11") (pin "Y14") (pinfunction "IO_L28P_2_Y14") (pintype "passive"))
    )
    (net (code "83") (name "unconnected-(U11C-IO_L29N_GCLK2_2-PadAF14)") (class "Default")
      (node (ref "U11") (pin "AF14") (pinfunction "IO_L29N_GCLK2_2_AF14") (pintype "passive"))
    )
    (net (code "84") (name "unconnected-(U11C-IO_L29P_GCLK3_2-PadAD14)") (class "Default")
      (node (ref "U11") (pin "AD14") (pinfunction "IO_L29P_GCLK3_2_AD14") (pintype "passive"))
    )
    (net (code "85") (name "unconnected-(U11C-IO_L30N_GCLK0_USERCCLK_2-PadAF13)") (class "Default")
      (node (ref "U11") (pin "AF13") (pinfunction "IO_L30N_GCLK0_USERCCLK_2_AF13") (pintype "passive"))
    )
    (net (code "86") (name "unconnected-(U11C-IO_L30P_GCLK1_D13_2-PadAE13)") (class "Default")
      (node (ref "U11") (pin "AE13") (pinfunction "IO_L30P_GCLK1_D13_2_AE13") (pintype "passive"))
    )
    (net (code "87") (name "unconnected-(U11C-IO_L31N_GCLK30_D15_2-PadAD13)") (class "Default")
      (node (ref "U11") (pin "AD13") (pinfunction "IO_L31N_GCLK30_D15_2_AD13") (pintype "passive"))
    )
    (net (code "88") (name "unconnected-(U11C-IO_L31P_GCLK31_D14_2-PadAC13)") (class "Default")
      (node (ref "U11") (pin "AC13") (pinfunction "IO_L31P_GCLK31_D14_2_AC13") (pintype "passive"))
    )
    (net (code "89") (name "unconnected-(U11C-IO_L32N_GCLK28_2-PadAF12)") (class "Default")
      (node (ref "U11") (pin "AF12") (pinfunction "IO_L32N_GCLK28_2_AF12") (pintype "passive"))
    )
    (net (code "90") (name "unconnected-(U11C-IO_L32P_GCLK29_2-PadAD12)") (class "Default")
      (node (ref "U11") (pin "AD12") (pinfunction "IO_L32P_GCLK29_2_AD12") (pintype "passive"))
    )
    (net (code "91") (name "unconnected-(U11C-IO_L41N_VREF_2-PadAC12)") (class "Default")
      (node (ref "U11") (pin "AC12") (pinfunction "IO_L41N_VREF_2_AC12") (pintype "passive"))
    )
    (net (code "92") (name "unconnected-(U11C-IO_L45N_2-PadAD11)") (class "Default")
      (node (ref "U11") (pin "AD11") (pinfunction "IO_L45N_2_AD11") (pintype "passive"))
    )
    (net (code "93") (name "unconnected-(U11C-IO_L45P_2-PadAC11)") (class "Default")
      (node (ref "U11") (pin "AC11") (pinfunction "IO_L45P_2_AC11") (pintype "passive"))
    )
    (net (code "94") (name "unconnected-(U11C-IO_L48N_RDWR_B_VREF_2-PadAF9)") (class "Default")
      (node (ref "U11") (pin "AF9") (pinfunction "IO_L48N_RDWR_B_VREF_2_AF9") (pintype "passive"))
    )
    (net (code "95") (name "unconnected-(U11C-IO_L48P_D7_2-PadAE9)") (class "Default")
      (node (ref "U11") (pin "AE9") (pinfunction "IO_L48P_D7_2_AE9") (pintype "passive"))
    )
    (net (code "96") (name "unconnected-(U11C-IO_L53N_2-PadAF8)") (class "Default")
      (node (ref "U11") (pin "AF8") (pinfunction "IO_L53N_2_AF8") (pintype "passive"))
    )
    (net (code "97") (name "unconnected-(U11C-IO_L53P_2-PadAD8)") (class "Default")
      (node (ref "U11") (pin "AD8") (pinfunction "IO_L53P_2_AD8") (pintype "passive"))
    )
    (net (code "98") (name "unconnected-(U11C-IO_L58N_2-PadAD9)") (class "Default")
      (node (ref "U11") (pin "AD9") (pinfunction "IO_L58N_2_AD9") (pintype "passive"))
    )
    (net (code "99") (name "unconnected-(U11C-IO_L58P_2-PadAC9)") (class "Default")
      (node (ref "U11") (pin "AC9") (pinfunction "IO_L58P_2_AC9") (pintype "passive"))
    )
    (net (code "100") (name "unconnected-(U11C-IO_L61N_VREF_2-PadAB9)") (class "Default")
      (node (ref "U11") (pin "AB9") (pinfunction "IO_L61N_VREF_2_AB9") (pintype "passive"))
    )
    (net (code "101") (name "unconnected-(U11C-IO_L61P_2-PadAA9)") (class "Default")
      (node (ref "U11") (pin "AA9") (pinfunction "IO_L61P_2_AA9") (pintype "passive"))
    )
    (net (code "102") (name "unconnected-(U11C-IO_L62N_D6_2-PadAF7)") (class "Default")
      (node (ref "U11") (pin "AF7") (pinfunction "IO_L62N_D6_2_AF7") (pintype "passive"))
    )
    (net (code "103") (name "unconnected-(U11C-IO_L62P_D5_2-PadAE7)") (class "Default")
      (node (ref "U11") (pin "AE7") (pinfunction "IO_L62P_D5_2_AE7") (pintype "passive"))
    )
    (net (code "104") (name "unconnected-(U11C-IO_L63N_2-PadAF6)") (class "Default")
      (node (ref "U11") (pin "AF6") (pinfunction "IO_L63N_2_AF6") (pintype "passive"))
    )
    (net (code "105") (name "unconnected-(U11C-IO_L63P_2-PadAD6)") (class "Default")
      (node (ref "U11") (pin "AD6") (pinfunction "IO_L63P_2_AD6") (pintype "passive"))
    )
    (net (code "106") (name "unconnected-(U11C-IO_L64N_D9_2-PadAF5)") (class "Default")
      (node (ref "U11") (pin "AF5") (pinfunction "IO_L64N_D9_2_AF5") (pintype "passive"))
    )
    (net (code "107") (name "unconnected-(U11C-IO_L64P_D8_2-PadAE5)") (class "Default")
      (node (ref "U11") (pin "AE5") (pinfunction "IO_L64P_D8_2_AE5") (pintype "passive"))
    )
    (net (code "108") (name "unconnected-(U13-NC-Pad1)") (class "Default")
      (node (ref "U13") (pin "1") (pinfunction "NC_1") (pintype "passive+no_connect"))
    )
    (net (code "109") (name "unconnected-(U14-NC-Pad1)") (class "Default")
      (node (ref "U14") (pin "1") (pinfunction "NC_1") (pintype "passive+no_connect"))
    )
  )
)
